# ADC.net
KiCad netlist of a schematic drawn in Altium Designer
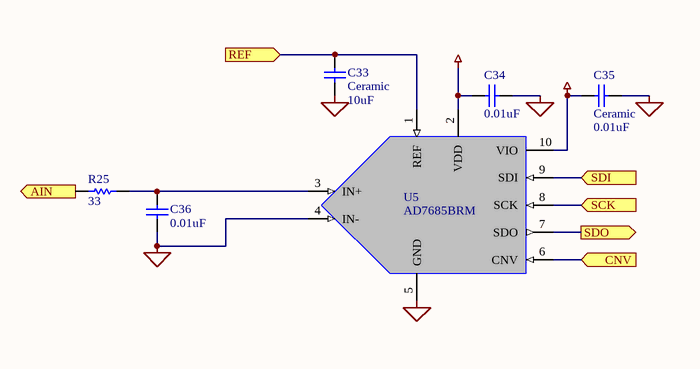
[diagram p0: ADC.SCHDOC]

(export (version "E")
  (design (tool "Eeschema 10.0.6"))
  (components
    (comp (ref "C33")
      (value "Ceramic")
      (footprint "0805")
      (description "Capacitor")
      (fields (field (name "ALTIUM_VALUE") "10uF") (field (name "PUBLISHER") "Altium Limited"))
      (libsource (lib "Miscellaneous Devices") (part "Cap"))
    )
    (comp (ref "C34")
      (value "0.01uF")
      (footprint "0603")
      (description "Capacitor")
      (fields (field (name "Comment") "Cap") (field (name "PUBLISHER") "Altium Limited"))
      (libsource (lib "Miscellaneous Devices") (part "Cap"))
    )
    (comp (ref "C35")
      (value "Ceramic")
      (footprint "0603")
      (description "Capacitor")
      (fields (field (name "ALTIUM_VALUE") "0.01uF") (field (name "PUBLISHER") "Altium Limited"))
      (libsource (lib "Miscellaneous Devices") (part "Cap"))
    )
    (comp (ref "C36")
      (value "0.01uF")
      (footprint "0603")
      (description "Capacitor")
      (fields (field (name "Comment") "Cap") (field (name "PUBLISHER") "Altium Limited"))
      (libsource (lib "Miscellaneous Devices") (part "Cap"))
    )
    (comp (ref "R25")
      (value "33")
      (footprint "0603")
      (description "Resistor")
      (fields (field (name "Comment") "Res1") (field (name "PUBLISHER") "Altium Limited"))
      (libsource (lib "Miscellaneous Devices") (part "Res1"))
    )
    (comp (ref "U5")
      (value "AD7685BRM")
      (footprint "AD RM-10")
      (description "AD 16-bit 250 kSPS ADC")
      (libsource (lib "parts") (part "AD7685"))
    )
  )
  (nets
    (net (code "1") (name "/AIN") (class "Default")
      (node (ref "R25") (pin "1") (pinfunction "1_1") (pintype "passive"))
    )
    (net (code "2") (name "/CNV") (class "Default")
      (node (ref "U5") (pin "6") (pinfunction "CNV_6") (pintype "input"))
    )
    (net (code "3") (name "/REF") (class "Default")
      (node (ref "C33") (pin "2") (pinfunction "2_2") (pintype "passive"))
      (node (ref "U5") (pin "1") (pinfunction "REF_1") (pintype "input"))
    )
    (net (code "4") (name "/SCK") (class "Default")
      (node (ref "U5") (pin "8") (pinfunction "SCK_8") (pintype "input"))
    )
    (net (code "5") (name "/SDI") (class "Default")
      (node (ref "U5") (pin "9") (pinfunction "SDI_9") (pintype "input"))
    )
    (net (code "6") (name "/SDO") (class "Default")
      (node (ref "U5") (pin "7") (pinfunction "SDO_7") (pintype "output"))
    )
    (net (code "7") (name "AGND") (class "Default")
      (node (ref "C33") (pin "1") (pinfunction "1_1") (pintype "passive"))
      (node (ref "C34") (pin "2") (pinfunction "2_2") (pintype "passive"))
      (node (ref "C35") (pin "1") (pinfunction "1_1") (pintype "passive"))
      (node (ref "C36") (pin "1") (pinfunction "1_1") (pintype "passive"))
      (node (ref "U5") (pin "4") (pinfunction "IN-_4") (pintype "input"))
      (node (ref "U5") (pin "5") (pinfunction "GND_5") (pintype "power_in"))
    )
    (net (code "8") (name "AVDD") (class "Default")
      (node (ref "C34") (pin "1") (pinfunction "1_1") (pintype "passive"))
      (node (ref "C35") (pin "2") (pinfunction "2_2") (pintype "passive"))
      (node (ref "U5") (pin "10") (pinfunction "VIO_10") (pintype "power_in"))
      (node (ref "U5") (pin "2") (pinfunction "VDD_2") (pintype "power_in"))
    )
    (net (code "9") (name "Net-(U5-IN+)") (class "Default")
      (node (ref "C36") (pin "2") (pinfunction "2_2") (pintype "passive"))
      (node (ref "R25") (pin "2") (pinfunction "2_2") (pintype "passive"))
      (node (ref "U5") (pin "3") (pinfunction "IN+_3") (pintype "input"))
    )
  )
)
